# STM32.net
KiCad netlist of a schematic drawn in Altium Designer
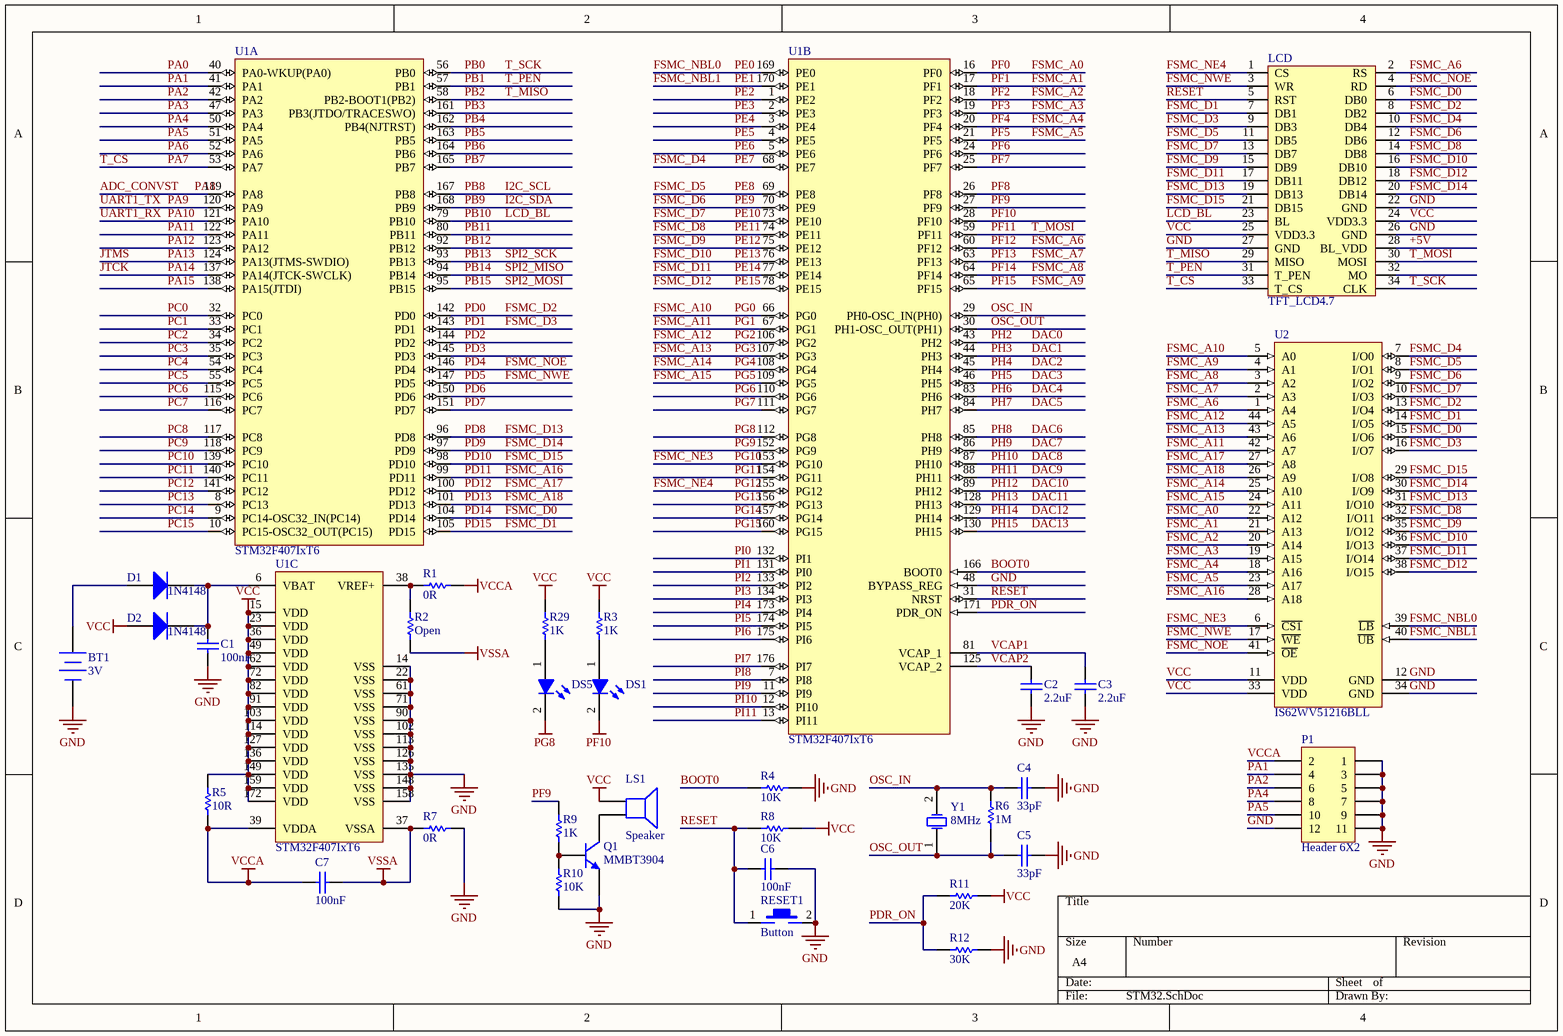
[diagram p0: STM32.SchDoc]

(export (version "E")
  (design (tool "Eeschema 10.0.6"))
  (components
    (comp (ref "BT1")
      (value "3V")
      (footprint "BAT-2")
      (description "Multicell Battery")
      (fields (field (name "PUBLISHER") "Altium Limited"))
      (libsource (lib "Miscellaneous Devices") (part "Battery"))
    )
    (comp (ref "C1")
      (value "100nF")
      (footprint "CAPC0603(1608)55_M")
      (libsource (lib "Slivy's ibrary") (part "CAP"))
    )
    (comp (ref "C2")
      (value "2.2uF")
      (footprint "CAPC0603(1608)55_M")
      (libsource (lib "Slivy's ibrary") (part "CAP"))
    )
    (comp (ref "C3")
      (value "2.2uF")
      (footprint "CAPC0603(1608)55_M")
      (libsource (lib "Slivy's ibrary") (part "CAP"))
    )
    (comp (ref "C4")
      (value "33pF")
      (footprint "CAPC0603(1608)55_M")
      (libsource (lib "Slivy's Library") (part "CAP"))
    )
    (comp (ref "C5")
      (value "33pF")
      (footprint "CAPC0603(1608)55_M")
      (libsource (lib "Slivy's Library") (part "CAP"))
    )
    (comp (ref "C6")
      (value "100nF")
      (footprint "CAPC0603(1608)55_M")
      (libsource (lib "Slivy's Library") (part "CAP"))
    )
    (comp (ref "C7")
      (value "100nF")
      (footprint "CAPC0603(1608)55_M")
      (libsource (lib "Slivy's Library") (part "CAP"))
    )
    (comp (ref "D1") (value "1N4148") (footprint "LL34") (libsource (lib "Slivy's ibrary") (part "Diode")))
    (comp (ref "D2") (value "1N4148") (footprint "LL34") (libsource (lib "Slivy's ibrary") (part "Diode")))
    (comp (ref "DS1")
      (value "LED-BLUE")
      (footprint "0603LED_BLUE_V")
      (libsource (lib "Slivy's Library") (part "LED-BLUE"))
    )
    (comp (ref "DS5")
      (value "LED-BLUE")
      (footprint "0603LED_BLUE_V")
      (libsource (lib "Slivy's Library") (part "LED-BLUE"))
    )
    (comp (ref "LCD")
      (value "TFT_LCD4.7")
      (footprint "DB2*17-3.5")
      (libsource (lib "Slivy's ibrary") (part "TFT_LCD4.7"))
    )
    (comp (ref "LS1")
      (value "Speaker")
      (footprint "Buzzer")
      (description "Loudspeaker")
      (fields (field (name "PUBLISHER") "Altium Limited"))
      (libsource (lib "Miscellaneous Devices") (part "Speaker"))
    )
    (comp (ref "P1")
      (value "Header 6X2")
      (footprint "HDR2X6")
      (description "Header, 6-Pin, Dual row")
      (fields (field (name "PUBLISHER") "Altium Limited"))
      (libsource (lib "Miscellaneous Connectors") (part "Header 6X2"))
    )
    (comp (ref "Q1")
      (value "MMBT3904")
      (footprint "SOT23_M")
      (description "NPN General Purpose Amplifier")
      (fields (field (name "PUBLISHER") "Altium Limited"))
      (libsource (lib "Slivy's ibrary") (part "MMBT3904"))
    )
    (comp (ref "R1")
      (value "0R")
      (footprint "RESC0603(1608)_M")
      (libsource (lib "Slivy's ibrary") (part "RES"))
    )
    (comp (ref "R2")
      (value "Open")
      (footprint "RESC0603(1608)_M")
      (libsource (lib "Slivy's ibrary") (part "RES"))
    )
    (comp (ref "R3")
      (value "1K")
      (footprint "RESC0603(1608)_M")
      (libsource (lib "Slivy's Library") (part "RES"))
    )
    (comp (ref "R4")
      (value "10K")
      (footprint "RESC0603(1608)_M")
      (libsource (lib "Slivy's Library") (part "RES"))
    )
    (comp (ref "R5")
      (value "10R")
      (footprint "RESC0603(1608)_M")
      (libsource (lib "Slivy's Library") (part "RES"))
    )
    (comp (ref "R6")
      (value "1M")
      (footprint "RESC0603(1608)_M")
      (libsource (lib "Slivy's Library") (part "RES"))
    )
    (comp (ref "R7")
      (value "0R")
      (footprint "RESC0603(1608)_M")
      (libsource (lib "Slivy's Library") (part "RES"))
    )
    (comp (ref "R8")
      (value "10K")
      (footprint "RESC0603(1608)_M")
      (libsource (lib "Slivy's Library") (part "RES"))
    )
    (comp (ref "R9")
      (value "1K")
      (footprint "RESC0603(1608)_M")
      (libsource (lib "Slivy's Library") (part "RES"))
    )
    (comp (ref "R10")
      (value "10K")
      (footprint "RESC0603(1608)_M")
      (libsource (lib "Slivy's Library") (part "RES"))
    )
    (comp (ref "R11")
      (value "20K")
      (footprint "RESC0603(1608)_M")
      (libsource (lib "Slivy's Library") (part "RES"))
    )
    (comp (ref "R12")
      (value "30K")
      (footprint "RESC0603(1608)_M")
      (libsource (lib "Slivy's Library") (part "RES"))
    )
    (comp (ref "R29")
      (value "1K")
      (footprint "RESC0603(1608)_M")
      (libsource (lib "Slivy's Library") (part "RES"))
    )
    (comp (ref "RESET1")
      (value "Button")
      (footprint "Button665")
      (libsource (lib "Slivy's ibrary") (part "Button"))
    )
    (comp (ref "U1")
      (value "STM32F407IxT6")
      (footprint "LQFP176")
      (libsource (lib "Slivy's Library") (part "STM32F407IxT6"))
    )
    (comp (ref "U2")
      (value "IS62WV51216BLL")
      (footprint "TSOP-2-44")
      (libsource (lib "Slivy's ibrary") (part "IS62WV51216BLL"))
    )
    (comp (ref "Y1")
      (value "8MHz")
      (footprint "HC-49S")
      (description "Crystal Oscillator")
      (fields (field (name "PUBLISHER") "Altium Limited"))
      (libsource (lib "Slivy's ibrary") (part "XTAL"))
    )
  )
  (nets
    (net (code "1") (name "/+5V") (class "Default")
      (node (ref "LCD") (pin "28") (pinfunction "BL_VDD_28") (pintype "passive"))
    )
    (net (code "2") (name "/ADC_CONVST") (class "Default")
      (node (ref "U1") (pin "119") (pinfunction "PA8_119") (pintype "bidirectional"))
    )
    (net (code "3") (name "/BOOT0") (class "Default")
      (node (ref "R4") (pin "2") (pinfunction "2_2") (pintype "passive"))
      (node (ref "U1") (pin "166") (pinfunction "BOOT0_166") (pintype "input"))
    )
    (net (code "4") (name "/DAC0") (class "Default")
      (node (ref "U1") (pin "43") (pinfunction "PH2_43") (pintype "bidirectional"))
    )
    (net (code "5") (name "/DAC1") (class "Default")
      (node (ref "U1") (pin "44") (pinfunction "PH3_44") (pintype "bidirectional"))
    )
    (net (code "6") (name "/DAC2") (class "Default")
      (node (ref "U1") (pin "45") (pinfunction "PH4_45") (pintype "bidirectional"))
    )
    (net (code "7") (name "/DAC3") (class "Default")
      (node (ref "U1") (pin "46") (pinfunction "PH5_46") (pintype "bidirectional"))
    )
    (net (code "8") (name "/DAC4") (class "Default")
      (node (ref "U1") (pin "83") (pinfunction "PH6_83") (pintype "bidirectional"))
    )
    (net (code "9") (name "/DAC5") (class "Default")
      (node (ref "U1") (pin "84") (pinfunction "PH7_84") (pintype "bidirectional"))
    )
    (net (code "10") (name "/DAC6") (class "Default")
      (node (ref "U1") (pin "85") (pinfunction "PH8_85") (pintype "bidirectional"))
    )
    (net (code "11") (name "/DAC7") (class "Default")
      (node (ref "U1") (pin "86") (pinfunction "PH9_86") (pintype "bidirectional"))
    )
    (net (code "12") (name "/DAC8") (class "Default")
      (node (ref "U1") (pin "87") (pinfunction "PH10_87") (pintype "bidirectional"))
    )
    (net (code "13") (name "/DAC9") (class "Default")
      (node (ref "U1") (pin "88") (pinfunction "PH11_88") (pintype "bidirectional"))
    )
    (net (code "14") (name "/DAC10") (class "Default")
      (node (ref "U1") (pin "89") (pinfunction "PH12_89") (pintype "bidirectional"))
    )
    (net (code "15") (name "/DAC11") (class "Default")
      (node (ref "U1") (pin "128") (pinfunction "PH13_128") (pintype "bidirectional"))
    )
    (net (code "16") (name "/DAC12") (class "Default")
      (node (ref "U1") (pin "129") (pinfunction "PH14_129") (pintype "bidirectional"))
    )
    (net (code "17") (name "/DAC13") (class "Default")
      (node (ref "U1") (pin "130") (pinfunction "PH15_130") (pintype "bidirectional"))
    )
    (net (code "18") (name "/FSMC_A0") (class "Default")
      (node (ref "U1") (pin "16") (pinfunction "PF0_16") (pintype "bidirectional"))
      (node (ref "U2") (pin "22") (pinfunction "A12_22") (pintype "input"))
    )
    (net (code "19") (name "/FSMC_A1") (class "Default")
      (node (ref "U1") (pin "17") (pinfunction "PF1_17") (pintype "bidirectional"))
      (node (ref "U2") (pin "21") (pinfunction "A13_21") (pintype "input"))
    )
    (net (code "20") (name "/FSMC_A2") (class "Default")
      (node (ref "U1") (pin "18") (pinfunction "PF2_18") (pintype "bidirectional"))
      (node (ref "U2") (pin "20") (pinfunction "A14_20") (pintype "input"))
    )
    (net (code "21") (name "/FSMC_A3") (class "Default")
      (node (ref "U1") (pin "19") (pinfunction "PF3_19") (pintype "bidirectional"))
      (node (ref "U2") (pin "19") (pinfunction "A15_19") (pintype "input"))
    )
    (net (code "22") (name "/FSMC_A4") (class "Default")
      (node (ref "U1") (pin "20") (pinfunction "PF4_20") (pintype "bidirectional"))
      (node (ref "U2") (pin "18") (pinfunction "A16_18") (pintype "input"))
    )
    (net (code "23") (name "/FSMC_A5") (class "Default")
      (node (ref "U1") (pin "21") (pinfunction "PF5_21") (pintype "bidirectional"))
      (node (ref "U2") (pin "23") (pinfunction "A17_23") (pintype "input"))
    )
    (net (code "24") (name "/FSMC_A6") (class "Default")
      (node (ref "LCD") (pin "2") (pinfunction "RS_2") (pintype "passive"))
      (node (ref "U1") (pin "60") (pinfunction "PF12_60") (pintype "bidirectional"))
      (node (ref "U2") (pin "1") (pinfunction "A4_1") (pintype "input"))
    )
    (net (code "25") (name "/FSMC_A7") (class "Default")
      (node (ref "U1") (pin "63") (pinfunction "PF13_63") (pintype "bidirectional"))
      (node (ref "U2") (pin "2") (pinfunction "A3_2") (pintype "input"))
    )
    (net (code "26") (name "/FSMC_A8") (class "Default")
      (node (ref "U1") (pin "64") (pinfunction "PF14_64") (pintype "bidirectional"))
      (node (ref "U2") (pin "3") (pinfunction "A2_3") (pintype "input"))
    )
    (net (code "27") (name "/FSMC_A9") (class "Default")
      (node (ref "U1") (pin "65") (pinfunction "PF15_65") (pintype "bidirectional"))
      (node (ref "U2") (pin "4") (pinfunction "A1_4") (pintype "input"))
    )
    (net (code "28") (name "/FSMC_A10") (class "Default")
      (node (ref "U1") (pin "66") (pinfunction "PG0_66") (pintype "bidirectional"))
      (node (ref "U2") (pin "5") (pinfunction "A0_5") (pintype "input"))
    )
    (net (code "29") (name "/FSMC_A11") (class "Default")
      (node (ref "U1") (pin "67") (pinfunction "PG1_67") (pintype "bidirectional"))
      (node (ref "U2") (pin "42") (pinfunction "A7_42") (pintype "input"))
    )
    (net (code "30") (name "/FSMC_A12") (class "Default")
      (node (ref "U1") (pin "106") (pinfunction "PG2_106") (pintype "bidirectional"))
      (node (ref "U2") (pin "44") (pinfunction "A5_44") (pintype "input"))
    )
    (net (code "31") (name "/FSMC_A13") (class "Default")
      (node (ref "U1") (pin "107") (pinfunction "PG3_107") (pintype "bidirectional"))
      (node (ref "U2") (pin "43") (pinfunction "A6_43") (pintype "input"))
    )
    (net (code "32") (name "/FSMC_A14") (class "Default")
      (node (ref "U1") (pin "108") (pinfunction "PG4_108") (pintype "bidirectional"))
      (node (ref "U2") (pin "25") (pinfunction "A10_25") (pintype "input"))
    )
    (net (code "33") (name "/FSMC_A15") (class "Default")
      (node (ref "U1") (pin "109") (pinfunction "PG5_109") (pintype "bidirectional"))
      (node (ref "U2") (pin "24") (pinfunction "A11_24") (pintype "input"))
    )
    (net (code "34") (name "/FSMC_A16") (class "Default")
      (node (ref "U1") (pin "99") (pinfunction "PD11_99") (pintype "bidirectional"))
      (node (ref "U2") (pin "28") (pinfunction "A18_28") (pintype "input"))
    )
    (net (code "35") (name "/FSMC_A17") (class "Default")
      (node (ref "U1") (pin "100") (pinfunction "PD12_100") (pintype "bidirectional"))
      (node (ref "U2") (pin "27") (pinfunction "A8_27") (pintype "input"))
    )
    (net (code "36") (name "/FSMC_A18") (class "Default")
      (node (ref "U1") (pin "101") (pinfunction "PD13_101") (pintype "bidirectional"))
      (node (ref "U2") (pin "26") (pinfunction "A9_26") (pintype "input"))
    )
    (net (code "37") (name "/FSMC_D0") (class "Default")
      (node (ref "LCD") (pin "6") (pinfunction "DB0_6") (pintype "passive"))
      (node (ref "U1") (pin "104") (pinfunction "PD14_104") (pintype "bidirectional"))
      (node (ref "U2") (pin "15") (pinfunction "I/O6_15") (pintype "bidirectional"))
    )
    (net (code "38") (name "/FSMC_D1") (class "Default")
      (node (ref "LCD") (pin "7") (pinfunction "DB1_7") (pintype "passive"))
      (node (ref "U1") (pin "105") (pinfunction "PD15_105") (pintype "bidirectional"))
      (node (ref "U2") (pin "14") (pinfunction "I/O5_14") (pintype "bidirectional"))
    )
    (net (code "39") (name "/FSMC_D2") (class "Default")
      (node (ref "LCD") (pin "8") (pinfunction "DB2_8") (pintype "passive"))
      (node (ref "U1") (pin "142") (pinfunction "PD0_142") (pintype "bidirectional"))
      (node (ref "U2") (pin "13") (pinfunction "I/O4_13") (pintype "bidirectional"))
    )
    (net (code "40") (name "/FSMC_D3") (class "Default")
      (node (ref "LCD") (pin "9") (pinfunction "DB3_9") (pintype "passive"))
      (node (ref "U1") (pin "143") (pinfunction "PD1_143") (pintype "bidirectional"))
      (node (ref "U2") (pin "16") (pinfunction "I/O7_16") (pintype "bidirectional"))
    )
    (net (code "41") (name "/FSMC_D4") (class "Default")
      (node (ref "LCD") (pin "10") (pinfunction "DB4_10") (pintype "passive"))
      (node (ref "U1") (pin "68") (pinfunction "PE7_68") (pintype "bidirectional"))
      (node (ref "U2") (pin "7") (pinfunction "I/O0_7") (pintype "bidirectional"))
    )
    (net (code "42") (name "/FSMC_D5") (class "Default")
      (node (ref "LCD") (pin "11") (pinfunction "DB5_11") (pintype "passive"))
      (node (ref "U1") (pin "69") (pinfunction "PE8_69") (pintype "bidirectional"))
      (node (ref "U2") (pin "8") (pinfunction "I/O1_8") (pintype "bidirectional"))
    )
    (net (code "43") (name "/FSMC_D6") (class "Default")
      (node (ref "LCD") (pin "12") (pinfunction "DB6_12") (pintype "passive"))
      (node (ref "U1") (pin "70") (pinfunction "PE9_70") (pintype "bidirectional"))
      (node (ref "U2") (pin "9") (pinfunction "I/O2_9") (pintype "bidirectional"))
    )
    (net (code "44") (name "/FSMC_D7") (class "Default")
      (node (ref "LCD") (pin "13") (pinfunction "DB7_13") (pintype "passive"))
      (node (ref "U1") (pin "73") (pinfunction "PE10_73") (pintype "bidirectional"))
      (node (ref "U2") (pin "10") (pinfunction "I/O3_10") (pintype "bidirectional"))
    )
    (net (code "45") (name "/FSMC_D8") (class "Default")
      (node (ref "LCD") (pin "14") (pinfunction "DB8_14") (pintype "passive"))
      (node (ref "U1") (pin "74") (pinfunction "PE11_74") (pintype "bidirectional"))
      (node (ref "U2") (pin "32") (pinfunction "I/O11_32") (pintype "bidirectional"))
    )
    (net (code "46") (name "/FSMC_D9") (class "Default")
      (node (ref "LCD") (pin "15") (pinfunction "DB9_15") (pintype "passive"))
      (node (ref "U1") (pin "75") (pinfunction "PE12_75") (pintype "bidirectional"))
      (node (ref "U2") (pin "35") (pinfunction "I/O12_35") (pintype "bidirectional"))
    )
    (net (code "47") (name "/FSMC_D10") (class "Default")
      (node (ref "LCD") (pin "16") (pinfunction "DB10_16") (pintype "passive"))
      (node (ref "U1") (pin "76") (pinfunction "PE13_76") (pintype "bidirectional"))
      (node (ref "U2") (pin "36") (pinfunction "I/O13_36") (pintype "bidirectional"))
    )
    (net (code "48") (name "/FSMC_D11") (class "Default")
      (node (ref "LCD") (pin "17") (pinfunction "DB11_17") (pintype "passive"))
      (node (ref "U1") (pin "77") (pinfunction "PE14_77") (pintype "bidirectional"))
      (node (ref "U2") (pin "37") (pinfunction "I/O14_37") (pintype "bidirectional"))
    )
    (net (code "49") (name "/FSMC_D12") (class "Default")
      (node (ref "LCD") (pin "18") (pinfunction "DB12_18") (pintype "passive"))
      (node (ref "U1") (pin "78") (pinfunction "PE15_78") (pintype "bidirectional"))
      (node (ref "U2") (pin "38") (pinfunction "I/O15_38") (pintype "bidirectional"))
    )
    (net (code "50") (name "/FSMC_D13") (class "Default")
      (node (ref "LCD") (pin "19") (pinfunction "DB13_19") (pintype "passive"))
      (node (ref "U1") (pin "96") (pinfunction "PD8_96") (pintype "bidirectional"))
      (node (ref "U2") (pin "31") (pinfunction "I/O10_31") (pintype "bidirectional"))
    )
    (net (code "51") (name "/FSMC_D14") (class "Default")
      (node (ref "LCD") (pin "20") (pinfunction "DB14_20") (pintype "passive"))
      (node (ref "U1") (pin "97") (pinfunction "PD9_97") (pintype "bidirectional"))
      (node (ref "U2") (pin "30") (pinfunction "I/O9_30") (pintype "bidirectional"))
    )
    (net (code "52") (name "/FSMC_D15") (class "Default")
      (node (ref "LCD") (pin "21") (pinfunction "DB15_21") (pintype "passive"))
      (node (ref "U1") (pin "98") (pinfunction "PD10_98") (pintype "bidirectional"))
      (node (ref "U2") (pin "29") (pinfunction "I/O8_29") (pintype "bidirectional"))
    )
    (net (code "53") (name "/FSMC_NBL0") (class "Default")
      (node (ref "U1") (pin "169") (pinfunction "PE0_169") (pintype "bidirectional"))
      (node (ref "U2") (pin "39") (pinfunction "~{LB}_39") (pintype "input"))
    )
    (net (code "54") (name "/FSMC_NBL1") (class "Default")
      (node (ref "U1") (pin "170") (pinfunction "PE1_170") (pintype "bidirectional"))
      (node (ref "U2") (pin "40") (pinfunction "~{UB}_40") (pintype "input"))
    )
    (net (code "55") (name "/FSMC_NE3") (class "Default")
      (node (ref "U1") (pin "153") (pinfunction "PG10_153") (pintype "bidirectional"))
      (node (ref "U2") (pin "6") (pinfunction "~{CS1}_6") (pintype "input"))
    )
    (net (code "56") (name "/FSMC_NE4") (class "Default")
      (node (ref "LCD") (pin "1") (pinfunction "CS_1") (pintype "passive"))
      (node (ref "U1") (pin "155") (pinfunction "PG12_155") (pintype "bidirectional"))
    )
    (net (code "57") (name "/FSMC_NOE") (class "Default")
      (node (ref "LCD") (pin "4") (pinfunction "RD_4") (pintype "passive"))
      (node (ref "U1") (pin "146") (pinfunction "PD4_146") (pintype "bidirectional"))
      (node (ref "U2") (pin "41") (pinfunction "~{OE}_41") (pintype "input"))
    )
    (net (code "58") (name "/FSMC_NWE") (class "Default")
      (node (ref "LCD") (pin "3") (pinfunction "WR_3") (pintype "passive"))
      (node (ref "U1") (pin "147") (pinfunction "PD5_147") (pintype "bidirectional"))
      (node (ref "U2") (pin "17") (pinfunction "~{WE}_17") (pintype "input"))
    )
    (net (code "59") (name "/I2C_SCL") (class "Default")
      (node (ref "U1") (pin "167") (pinfunction "PB8_167") (pintype "bidirectional"))
    )
    (net (code "60") (name "/I2C_SDA") (class "Default")
      (node (ref "U1") (pin "168") (pinfunction "PB9_168") (pintype "bidirectional"))
    )
    (net (code "61") (name "/JTCK") (class "Default")
      (node (ref "U1") (pin "137") (pinfunction "PA14(JTCK-SWCLK)_137") (pintype "bidirectional"))
    )
    (net (code "62") (name "/JTMS") (class "Default")
      (node (ref "U1") (pin "124") (pinfunction "PA13(JTMS-SWDIO)_124") (pintype "bidirectional"))
    )
    (net (code "63") (name "/LCD_BL") (class "Default")
      (node (ref "LCD") (pin "23") (pinfunction "BL_23") (pintype "passive"))
      (node (ref "U1") (pin "79") (pinfunction "PB10_79") (pintype "bidirectional"))
    )
    (net (code "64") (name "/OSC_IN") (class "Default")
      (node (ref "C4") (pin "1") (pinfunction "1_1") (pintype "passive"))
      (node (ref "R6") (pin "2") (pinfunction "2_2") (pintype "passive"))
      (node (ref "U1") (pin "29") (pinfunction "PH0-OSC_IN(PH0)_29") (pintype "bidirectional"))
      (node (ref "Y1") (pin "2") (pinfunction "OSC2_2") (pintype "passive"))
    )
    (net (code "65") (name "/OSC_OUT") (class "Default")
      (node (ref "C5") (pin "1") (pinfunction "1_1") (pintype "passive"))
      (node (ref "R6") (pin "1") (pinfunction "1_1") (pintype "passive"))
      (node (ref "U1") (pin "30") (pinfunction "PH1-OSC_OUT(PH1)_30") (pintype "bidirectional"))
      (node (ref "Y1") (pin "1") (pinfunction "OSC1_1") (pintype "passive"))
    )
    (net (code "66") (name "/PA0") (class "Default")
      (node (ref "U1") (pin "40") (pinfunction "PA0-WKUP(PA0)_40") (pintype "bidirectional"))
    )
    (net (code "67") (name "/PA1") (class "Default")
      (node (ref "P1") (pin "4") (pinfunction "4_4") (pintype "passive"))
      (node (ref "U1") (pin "41") (pinfunction "PA1_41") (pintype "bidirectional"))
    )
    (net (code "68") (name "/PA2") (class "Default")
      (node (ref "P1") (pin "6") (pinfunction "6_6") (pintype "passive"))
      (node (ref "U1") (pin "42") (pinfunction "PA2_42") (pintype "bidirectional"))
    )
    (net (code "69") (name "/PA3") (class "Default")
      (node (ref "U1") (pin "47") (pinfunction "PA3_47") (pintype "bidirectional"))
    )
    (net (code "70") (name "/PA4") (class "Default")
      (node (ref "P1") (pin "8") (pinfunction "8_8") (pintype "passive"))
      (node (ref "U1") (pin "50") (pinfunction "PA4_50") (pintype "bidirectional"))
    )
    (net (code "71") (name "/PA5") (class "Default")
      (node (ref "P1") (pin "10") (pinfunction "10_10") (pintype "passive"))
      (node (ref "U1") (pin "51") (pinfunction "PA5_51") (pintype "bidirectional"))
    )
    (net (code "72") (name "/PA6") (class "Default")
      (node (ref "U1") (pin "52") (pinfunction "PA6_52") (pintype "bidirectional"))
    )
    (net (code "73") (name "/PA7") (class "Default")
      (node (ref "LCD") (pin "33") (pinfunction "T_CS_33") (pintype "passive"))
      (node (ref "U1") (pin "53") (pinfunction "PA7_53") (pintype "bidirectional"))
    )
    (net (code "74") (name "/PA9") (class "Default")
      (node (ref "U1") (pin "120") (pinfunction "PA9_120") (pintype "bidirectional"))
    )
    (net (code "75") (name "/PA10") (class "Default")
      (node (ref "U1") (pin "121") (pinfunction "PA10_121") (pintype "bidirectional"))
    )
    (net (code "76") (name "/PA11") (class "Default")
      (node (ref "U1") (pin "122") (pinfunction "PA11_122") (pintype "bidirectional"))
    )
    (net (code "77") (name "/PA12") (class "Default")
      (node (ref "U1") (pin "123") (pinfunction "PA12_123") (pintype "bidirectional"))
    )
    (net (code "78") (name "/PA15") (class "Default")
      (node (ref "U1") (pin "138") (pinfunction "PA15(JTDI)_138") (pintype "bidirectional"))
    )
    (net (code "79") (name "/PB0") (class "Default")
      (node (ref "LCD") (pin "34") (pinfunction "CLK_34") (pintype "passive"))
      (node (ref "U1") (pin "56") (pinfunction "PB0_56") (pintype "bidirectional"))
    )
    (net (code "80") (name "/PB1") (class "Default")
      (node (ref "LCD") (pin "31") (pinfunction "T_PEN_31") (pintype "passive"))
      (node (ref "U1") (pin "57") (pinfunction "PB1_57") (pintype "bidirectional"))
    )
    (net (code "81") (name "/PB2") (class "Default")
      (node (ref "LCD") (pin "29") (pinfunction "MISO_29") (pintype "passive"))
      (node (ref "U1") (pin "58") (pinfunction "PB2-BOOT1(PB2)_58") (pintype "bidirectional"))
    )
    (net (code "82") (name "/PB3") (class "Default")
      (node (ref "U1") (pin "161") (pinfunction "PB3(JTDO/TRACESWO)_161") (pintype "bidirectional"))
    )
    (net (code "83") (name "/PB4") (class "Default")
      (node (ref "U1") (pin "162") (pinfunction "PB4(NJTRST)_162") (pintype "bidirectional"))
    )
    (net (code "84") (name "/PB5") (class "Default")
      (node (ref "U1") (pin "163") (pinfunction "PB5_163") (pintype "bidirectional"))
    )
    (net (code "85") (name "/PB6") (class "Default")
      (node (ref "U1") (pin "164") (pinfunction "PB6_164") (pintype "bidirectional"))
    )
    (net (code "86") (name "/PB7") (class "Default")
      (node (ref "U1") (pin "165") (pinfunction "PB7_165") (pintype "bidirectional"))
    )
    (net (code "87") (name "/PB11") (class "Default")
      (node (ref "U1") (pin "80") (pinfunction "PB11_80") (pintype "bidirectional"))
    )
    (net (code "88") (name "/PB12") (class "Default")
      (node (ref "U1") (pin "92") (pinfunction "PB12_92") (pintype "bidirectional"))
    )
    (net (code "89") (name "/PB13") (class "Default")
      (node (ref "U1") (pin "93") (pinfunction "PB13_93") (pintype "bidirectional"))
    )
    (net (code "90") (name "/PB14") (class "Default")
      (node (ref "U1") (pin "94") (pinfunction "PB14_94") (pintype "bidirectional"))
    )
    (net (code "91") (name "/PB15") (class "Default")
      (node (ref "U1") (pin "95") (pinfunction "PB15_95") (pintype "bidirectional"))
    )
    (net (code "92") (name "/PC0") (class "Default")
      (node (ref "U1") (pin "32") (pinfunction "PC0_32") (pintype "bidirectional"))
    )
    (net (code "93") (name "/PC1") (class "Default")
      (node (ref "U1") (pin "33") (pinfunction "PC1_33") (pintype "bidirectional"))
    )
    (net (code "94") (name "/PC2") (class "Default")
      (node (ref "U1") (pin "34") (pinfunction "PC2_34") (pintype "bidirectional"))
    )
    (net (code "95") (name "/PC3") (class "Default")
      (node (ref "U1") (pin "35") (pinfunction "PC3_35") (pintype "bidirectional"))
    )
    (net (code "96") (name "/PC4") (class "Default")
      (node (ref "U1") (pin "54") (pinfunction "PC4_54") (pintype "bidirectional"))
    )
    (net (code "97") (name "/PC5") (class "Default")
      (node (ref "U1") (pin "55") (pinfunction "PC5_55") (pintype "bidirectional"))
    )
    (net (code "98") (name "/PC6") (class "Default")
      (node (ref "U1") (pin "115") (pinfunction "PC6_115") (pintype "bidirectional"))
    )
    (net (code "99") (name "/PC7") (class "Default")
      (node (ref "U1") (pin "116") (pinfunction "PC7_116") (pintype "bidirectional"))
    )
    (net (code "100") (name "/PC8") (class "Default")
      (node (ref "U1") (pin "117") (pinfunction "PC8_117") (pintype "bidirectional"))
    )
    (net (code "101") (name "/PC9") (class "Default")
      (node (ref "U1") (pin "118") (pinfunction "PC9_118") (pintype "bidirectional"))
    )
    (net (code "102") (name "/PC10") (class "Default")
      (node (ref "U1") (pin "139") (pinfunction "PC10_139") (pintype "bidirectional"))
    )
    (net (code "103") (name "/PC11") (class "Default")
      (node (ref "U1") (pin "140") (pinfunction "PC11_140") (pintype "bidirectional"))
    )
    (net (code "104") (name "/PC12") (class "Default")
      (node (ref "U1") (pin "141") (pinfunction "PC12_141") (pintype "bidirectional"))
    )
    (net (code "105") (name "/PC13") (class "Default")
      (node (ref "U1") (pin "8") (pinfunction "PC13_8") (pintype "bidirectional"))
    )
    (net (code "106") (name "/PC14") (class "Default")
      (node (ref "U1") (pin "9") (pinfunction "PC14-OSC32_IN(PC14)_9") (pintype "bidirectional"))
    )
    (net (code "107") (name "/PC15") (class "Default")
      (node (ref "U1") (pin "10") (pinfunction "PC15-OSC32_OUT(PC15)_10") (pintype "bidirectional"))
    )
    (net (code "108") (name "/PD2") (class "Default")
      (node (ref "U1") (pin "144") (pinfunction "PD2_144") (pintype "bidirectional"))
    )
    (net (code "109") (name "/PD3") (class "Default")
      (node (ref "U1") (pin "145") (pinfunction "PD3_145") (pintype "bidirectional"))
    )
    (net (code "110") (name "/PD6") (class "Default")
      (node (ref "U1") (pin "150") (pinfunction "PD6_150") (pintype "bidirectional"))
    )
    (net (code "111") (name "/PD7") (class "Default")
      (node (ref "U1") (pin "151") (pinfunction "PD7_151") (pintype "bidirectional"))
    )
    (net (code "112") (name "/PDR_ON") (class "Default")
      (node (ref "R11") (pin "2") (pinfunction "2_2") (pintype "passive"))
      (node (ref "R12") (pin "2") (pinfunction "2_2") (pintype "passive"))
      (node (ref "U1") (pin "171") (pinfunction "PDR_ON_171") (pintype "input"))
    )
    (net (code "113") (name "/PE2") (class "Default")
      (node (ref "U1") (pin "1") (pinfunction "PE2_1") (pintype "bidirectional"))
    )
    (net (code "114") (name "/PE3") (class "Default")
      (node (ref "U1") (pin "2") (pinfunction "PE3_2") (pintype "bidirectional"))
    )
    (net (code "115") (name "/PE4") (class "Default")
      (node (ref "U1") (pin "3") (pinfunction "PE4_3") (pintype "bidirectional"))
    )
    (net (code "116") (name "/PE5") (class "Default")
      (node (ref "U1") (pin "4") (pinfunction "PE5_4") (pintype "bidirectional"))
    )
    (net (code "117") (name "/PE6") (class "Default")
      (node (ref "U1") (pin "5") (pinfunction "PE6_5") (pintype "bidirectional"))
    )
    (net (code "118") (name "/PF6") (class "Default")
      (node (ref "U1") (pin "24") (pinfunction "PF6_24") (pintype "bidirectional"))
    )
    (net (code "119") (name "/PF7") (class "Default")
      (node (ref "U1") (pin "25") (pinfunction "PF7_25") (pintype "bidirectional"))
    )
    (net (code "120") (name "/PF8") (class "Default")
      (node (ref "U1") (pin "26") (pinfunction "PF8_26") (pintype "bidirectional"))
    )
    (net (code "121") (name "/PF9") (class "Default")
      (node (ref "R9") (pin "2") (pinfunction "2_2") (pintype "passive"))
      (node (ref "U1") (pin "27") (pinfunction "PF9_27") (pintype "bidirectional"))
    )
    (net (code "122") (name "/PF11") (class "Default")
      (node (ref "LCD") (pin "30") (pinfunction "MOSI_30") (pintype "passive"))
      (node (ref "U1") (pin "59") (pinfunction "PF11_59") (pintype "bidirectional"))
    )
    (net (code "123") (name "/PG6") (class "Default")
      (node (ref "U1") (pin "110") (pinfunction "PG6_110") (pintype "bidirectional"))
    )
    (net (code "124") (name "/PG7") (class "Default")
      (node (ref "U1") (pin "111") (pinfunction "PG7_111") (pintype "bidirectional"))
    )
    (net (code "125") (name "/PG9") (class "Default")
      (node (ref "U1") (pin "152") (pinfunction "PG9_152") (pintype "bidirectional"))
    )
    (net (code "126") (name "/PG11") (class "Default")
      (node (ref "U1") (pin "154") (pinfunction "PG11_154") (pintype "bidirectional"))
    )
    (net (code "127") (name "/PG13") (class "Default")
      (node (ref "U1") (pin "156") (pinfunction "PG13_156") (pintype "bidirectional"))
    )
    (net (code "128") (name "/PG14") (class "Default")
      (node (ref "U1") (pin "157") (pinfunction "PG14_157") (pintype "bidirectional"))
    )
    (net (code "129") (name "/PG15") (class "Default")
      (node (ref "U1") (pin "160") (pinfunction "PG15_160") (pintype "bidirectional"))
    )
    (net (code "130") (name "/PI0") (class "Default")
      (node (ref "U1") (pin "132") (pinfunction "PI1_132") (pintype "bidirectional"))
    )
    (net (code "131") (name "/PI1") (class "Default")
      (node (ref "U1") (pin "131") (pinfunction "PI0_131") (pintype "bidirectional"))
    )
    (net (code "132") (name "/PI2") (class "Default")
      (node (ref "U1") (pin "133") (pinfunction "PI2_133") (pintype "bidirectional"))
    )
    (net (code "133") (name "/PI3") (class "Default")
      (node (ref "U1") (pin "134") (pinfunction "PI3_134") (pintype "bidirectional"))
    )
    (net (code "134") (name "/PI4") (class "Default")
      (node (ref "U1") (pin "173") (pinfunction "PI4_173") (pintype "bidirectional"))
    )
    (net (code "135") (name "/PI5") (class "Default")
      (node (ref "U1") (pin "174") (pinfunction "PI5_174") (pintype "bidirectional"))
    )
    (net (code "136") (name "/PI6") (class "Default")
      (node (ref "U1") (pin "175") (pinfunction "PI6_175") (pintype "bidirectional"))
    )
    (net (code "137") (name "/PI7") (class "Default")
      (node (ref "U1") (pin "176") (pinfunction "PI7_176") (pintype "bidirectional"))
    )
    (net (code "138") (name "/PI8") (class "Default")
      (node (ref "U1") (pin "7") (pinfunction "PI8_7") (pintype "bidirectional"))
    )
    (net (code "139") (name "/PI9") (class "Default")
      (node (ref "U1") (pin "11") (pinfunction "PI9_11") (pintype "bidirectional"))
    )
    (net (code "140") (name "/PI10") (class "Default")
      (node (ref "U1") (pin "12") (pinfunction "PI10_12") (pintype "bidirectional"))
    )
    (net (code "141") (name "/PI11") (class "Default")
      (node (ref "U1") (pin "13") (pinfunction "PI11_13") (pintype "bidirectional"))
    )
    (net (code "142") (name "/RESET") (class "Default")
      (node (ref "C6") (pin "1") (pinfunction "1_1") (pintype "passive"))
      (node (ref "LCD") (pin "5") (pinfunction "RST_5") (pintype "passive"))
      (node (ref "R8") (pin "2") (pinfunction "2_2") (pintype "passive"))
      (node (ref "RESET1") (pin "1") (pinfunction "1_1") (pintype "passive"))
      (node (ref "U1") (pin "31") (pinfunction "NRST_31") (pintype "bidirectional"))
    )
    (net (code "143") (name "/VCAP1") (class "Default")
      (node (ref "C3") (pin "2") (pinfunction "2_2") (pintype "passive"))
      (node (ref "U1") (pin "81") (pinfunction "VCAP_1_81") (pintype "power_in"))
    )
    (net (code "144") (name "/VCAP2") (class "Default")
      (node (ref "C2") (pin "2") (pinfunction "2_2") (pintype "passive"))
      (node (ref "U1") (pin "125") (pinfunction "VCAP_2_125") (pintype "power_in"))
    )
    (net (code "145") (name "GND") (class "Default")
      (node (ref "BT1") (pin "2") (pinfunction "-_2") (pintype "passive"))
      (node (ref "C1") (pin "2") (pinfunction "2_2") (pintype "passive"))
      (node (ref "C2") (pin "1") (pinfunction "1_1") (pintype "passive"))
      (node (ref "C3") (pin "1") (pinfunction "1_1") (pintype "passive"))
      (node (ref "C4") (pin "2") (pinfunction "2_2") (pintype "passive"))
      (node (ref "C5") (pin "2") (pinfunction "2_2") (pintype "passive"))
      (node (ref "C6") (pin "2") (pinfunction "2_2") (pintype "passive"))
      (node (ref "LCD") (pin "22") (pinfunction "GND_22") (pintype "passive"))
      (node (ref "LCD") (pin "26") (pinfunction "GND_26") (pintype "passive"))
      (node (ref "LCD") (pin "27") (pinfunction "GND_27") (pintype "passive"))
      (node (ref "P1") (pin "1") (pinfunction "1_1") (pintype "passive"))
      (node (ref "P1") (pin "11") (pinfunction "11_11") (pintype "passive"))
      (node (ref "P1") (pin "12") (pinfunction "12_12") (pintype "passive"))
      (node (ref "P1") (pin "3") (pinfunction "3_3") (pintype "passive"))
      (node (ref "P1") (pin "5") (pinfunction "5_5") (pintype "passive"))
      (node (ref "P1") (pin "7") (pinfunction "7_7") (pintype "passive"))
      (node (ref "P1") (pin "9") (pinfunction "9_9") (pintype "passive"))
      (node (ref "Q1") (pin "2") (pinfunction "E_2") (pintype "passive"))
      (node (ref "R10") (pin "1") (pinfunction "1_1") (pintype "passive"))
      (node (ref "R12") (pin "1") (pinfunction "1_1") (pintype "passive"))
      (node (ref "R4") (pin "1") (pinfunction "1_1") (pintype "passive"))
      (node (ref "R7") (pin "1") (pinfunction "1_1") (pintype "passive"))
      (node (ref "RESET1") (pin "2") (pinfunction "2_2") (pintype "passive"))
      (node (ref "U1") (pin "102") (pinfunction "VSS_102") (pintype "power_in"))
      (node (ref "U1") (pin "113") (pinfunction "VSS_113") (pintype "power_in"))
      (node (ref "U1") (pin "126") (pinfunction "VSS_126") (pintype "power_in"))
      (node (ref "U1") (pin "135") (pinfunction "VSS_135") (pintype "power_in"))
      (node (ref "U1") (pin "14") (pinfunction "VSS_14") (pintype "power_in"))
      (node (ref "U1") (pin "148") (pinfunction "VSS_148") (pintype "power_in"))
      (node (ref "U1") (pin "158") (pinfunction "VSS_158") (pintype "power_in"))
      (node (ref "U1") (pin "22") (pinfunction "VSS_22") (pintype "power_in"))
      (node (ref "U1") (pin "48") (pinfunction "BYPASS_REG_48") (pintype "input"))
      (node (ref "U1") (pin "61") (pinfunction "VSS_61") (pintype "power_in"))
      (node (ref "U1") (pin "71") (pinfunction "VSS_71") (pintype "power_in"))
      (node (ref "U1") (pin "90") (pinfunction "VSS_90") (pintype "power_in"))
      (node (ref "U2") (pin "12") (pinfunction "GND_12") (pintype "power_in"))
      (node (ref "U2") (pin "34") (pinfunction "GND_34") (pintype "power_in"))
    )
    (net (code "146") (name "Net-(BT1-+)") (class "Default")
      (node (ref "BT1") (pin "1") (pinfunction "+_1") (pintype "passive"))
      (node (ref "D1") (pin "2") (pinfunction "A_2") (pintype "passive"))
    )
    (net (code "147") (name "Net-(D1-K)") (class "Default")
      (node (ref "C1") (pin "1") (pinfunction "1_1") (pintype "passive"))
      (node (ref "D1") (pin "1") (pinfunction "K_1") (pintype "passive"))
      (node (ref "D2") (pin "1") (pinfunction "K_1") (pintype "passive"))
      (node (ref "U1") (pin "6") (pinfunction "VBAT_6") (pintype "power_in"))
    )
    (net (code "148") (name "Net-(DS1-A)") (class "Default")
      (node (ref "DS1") (pin "1") (pinfunction "A_1") (pintype "passive"))
      (node (ref "R3") (pin "1") (pinfunction "1_1") (pintype "passive"))
    )
    (net (code "149") (name "Net-(DS5-A)") (class "Default")
      (node (ref "DS5") (pin "1") (pinfunction "A_1") (pintype "passive"))
      (node (ref "R29") (pin "1") (pinfunction "1_1") (pintype "passive"))
    )
    (net (code "150") (name "Net-(Q1-B)") (class "Default")
      (node (ref "Q1") (pin "1") (pinfunction "B_1") (pintype "passive"))
      (node (ref "R10") (pin "2") (pinfunction "2_2") (pintype "passive"))
      (node (ref "R9") (pin "1") (pinfunction "1_1") (pintype "passive"))
    )
    (net (code "151") (name "Net-(Q1-C)") (class "Default")
      (node (ref "LS1") (pin "2") (pinfunction "2_2") (pintype "passive"))
      (node (ref "Q1") (pin "3") (pinfunction "C_3") (pintype "passive"))
    )
    (net (code "152") (name "Net-(U1C-VREF+)") (class "Default")
      (node (ref "R1") (pin "2") (pinfunction "2_2") (pintype "passive"))
      (node (ref "R2") (pin "2") (pinfunction "2_2") (pintype "passive"))
      (node (ref "U1") (pin "38") (pinfunction "VREF+_38") (pintype "power_in"))
    )
    (net (code "153") (name "PF10") (class "Default")
      (node (ref "DS1") (pin "2") (pinfunction "K_2") (pintype "passive"))
      (node (ref "U1") (pin "28") (pinfunction "PF10_28") (pintype "bidirectional"))
    )
    (net (code "154") (name "PG8") (class "Default")
      (node (ref "DS5") (pin "2") (pinfunction "K_2") (pintype "passive"))
      (node (ref "U1") (pin "112") (pinfunction "PG8_112") (pintype "bidirectional"))
    )
    (net (code "155") (name "VCC") (class "Default")
      (node (ref "D2") (pin "2") (pinfunction "A_2") (pintype "passive"))
      (node (ref "LCD") (pin "24") (pinfunction "VDD3.3_24") (pintype "passive"))
      (node (ref "LCD") (pin "25") (pinfunction "VDD3.3_25") (pintype "passive"))
      (node (ref "LS1") (pin "1") (pinfunction "1_1") (pintype "passive"))
      (node (ref "R11") (pin "1") (pinfunction "1_1") (pintype "passive"))
      (node (ref "R29") (pin "2") (pinfunction "2_2") (pintype "passive"))
      (node (ref "R3") (pin "2") (pinfunction "2_2") (pintype "passive"))
      (node (ref "R5") (pin "2") (pinfunction "2_2") (pintype "passive"))
      (node (ref "R8") (pin "1") (pinfunction "1_1") (pintype "passive"))
      (node (ref "U1") (pin "103") (pinfunction "VDD_103") (pintype "power_in"))
      (node (ref "U1") (pin "114") (pinfunction "VDD_114") (pintype "power_in"))
      (node (ref "U1") (pin "127") (pinfunction "VDD_127") (pintype "power_in"))
      (node (ref "U1") (pin "136") (pinfunction "VDD_136") (pintype "power_in"))
      (node (ref "U1") (pin "149") (pinfunction "VDD_149") (pintype "power_in"))
      (node (ref "U1") (pin "15") (pinfunction "VDD_15") (pintype "power_in"))
      (node (ref "U1") (pin "159") (pinfunction "VDD_159") (pintype "power_in"))
      (node (ref "U1") (pin "172") (pinfunction "VDD_172") (pintype "power_in"))
      (node (ref "U1") (pin "23") (pinfunction "VDD_23") (pintype "power_in"))
      (node (ref "U1") (pin "36") (pinfunction "VDD_36") (pintype "power_in"))
      (node (ref "U1") (pin "49") (pinfunction "VDD_49") (pintype "power_in"))
      (node (ref "U1") (pin "62") (pinfunction "VDD_62") (pintype "power_in"))
      (node (ref "U1") (pin "72") (pinfunction "VDD_72") (pintype "power_in"))
      (node (ref "U1") (pin "82") (pinfunction "VDD_82") (pintype "power_in"))
      (node (ref "U1") (pin "91") (pinfunction "VDD_91") (pintype "power_in"))
      (node (ref "U2") (pin "11") (pinfunction "VDD_11") (pintype "power_in"))
      (node (ref "U2") (pin "33") (pinfunction "VDD_33") (pintype "power_in"))
    )
    (net (code "156") (name "VCCA") (class "Default")
      (node (ref "C7") (pin "1") (pinfunction "1_1") (pintype "passive"))
      (node (ref "P1") (pin "2") (pinfunction "2_2") (pintype "passive"))
      (node (ref "R1") (pin "1") (pinfunction "1_1") (pintype "passive"))
      (node (ref "R5") (pin "1") (pinfunction "1_1") (pintype "passive"))
      (node (ref "U1") (pin "39") (pinfunction "VDDA_39") (pintype "power_in"))
    )
    (net (code "157") (name "VSSA") (class "Default")
      (node (ref "C7") (pin "2") (pinfunction "2_2") (pintype "passive"))
      (node (ref "R2") (pin "1") (pinfunction "1_1") (pintype "passive"))
      (node (ref "R7") (pin "2") (pinfunction "2_2") (pintype "passive"))
      (node (ref "U1") (pin "37") (pinfunction "VSSA_37") (pintype "power_in"))
    )
    (net (code "158") (name "unconnected-(LCD-MO-Pad32)") (class "Default")
      (node (ref "LCD") (pin "32") (pinfunction "MO_32") (pintype "passive"))
    )
  )
)
